# schem5.net
KiCad netlist of a schematic drawn in EAGLE
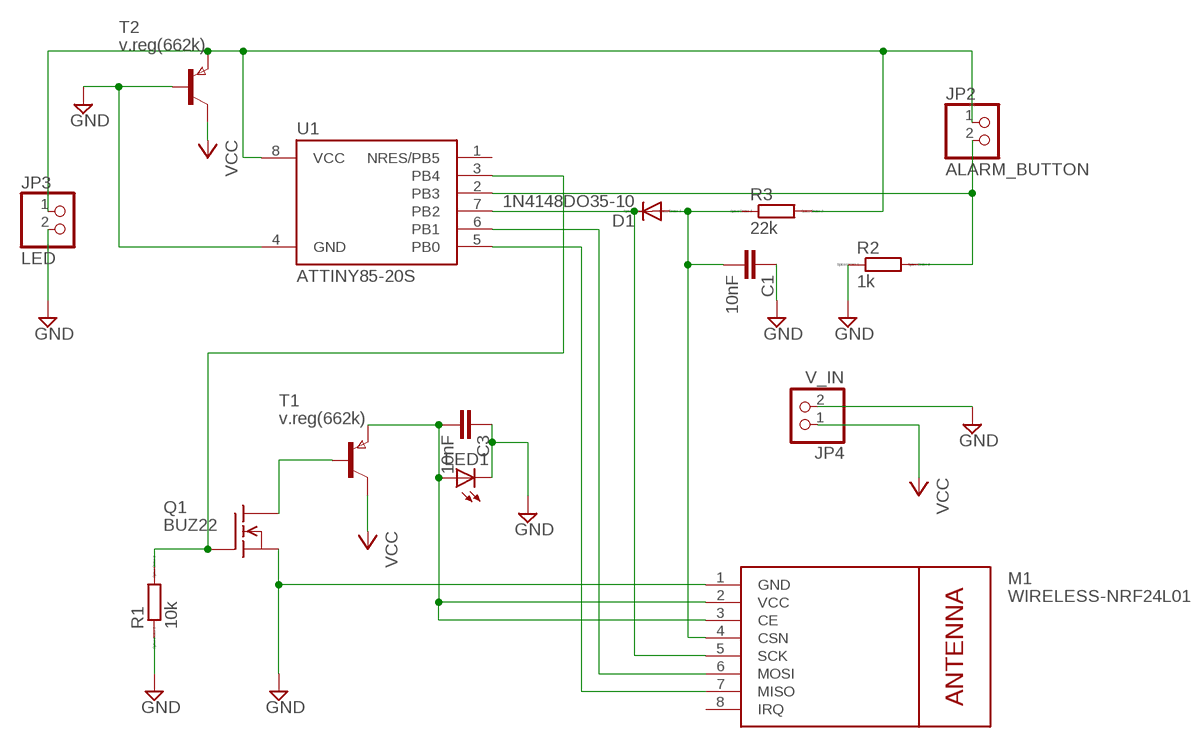
[diagram p0: schematic, sheet 1]

(export (version "E")
  (design (tool "Eeschema 10.0.6"))
  (components
    (comp (ref "C1")
      (value "10nF")
      (footprint "eagle-import:C2.5-2")
      (libsource (lib "eagle-import") (part "C2.5/2"))
    )
    (comp (ref "C3")
      (value "10nF")
      (footprint "eagle-import:C2.5-2")
      (libsource (lib "eagle-import") (part "C2.5/2"))
    )
    (comp (ref "D1")
      (value "1N4148DO35-10")
      (footprint "eagle-import:DO35-10")
      (libsource (lib "eagle-import") (part "1N4148DO35-10"))
    )
    (comp (ref "JP2")
      (value "ALARM_BUTTON")
      (footprint "eagle-import:1X02")
      (libsource (lib "eagle-import") (part "PINHD-1X2"))
    )
    (comp (ref "JP3")
      (value "LED")
      (footprint "eagle-import:1X02")
      (libsource (lib "eagle-import") (part "PINHD-1X2"))
    )
    (comp (ref "JP4")
      (value "V_IN")
      (footprint "eagle-import:1X02")
      (libsource (lib "eagle-import") (part "PINHD-1X2"))
    )
    (comp (ref "LED1")
      (value "LED5MM")
      (footprint "eagle-import:LED5MM")
      (libsource (lib "eagle-import") (part "LED5MM"))
    )
    (comp (ref "M1")
      (value "WIRELESS-NRF24L01")
      (footprint "eagle-import:WIRELESS-NRF24L01")
      (libsource (lib "eagle-import") (part "WIRELESS-NRF24L01"))
    )
    (comp (ref "Q1")
      (value "BUZ22")
      (footprint "eagle-import:TO220")
      (libsource (lib "eagle-import") (part "BUZ22"))
    )
    (comp (ref "R1")
      (value "10k")
      (footprint "eagle-import:0204_7")
      (libsource (lib "eagle-import") (part "R0204/7"))
    )
    (comp (ref "R2")
      (value "1k")
      (footprint "eagle-import:0204_7")
      (libsource (lib "eagle-import") (part "R0204/7"))
    )
    (comp (ref "R3")
      (value "22k")
      (footprint "eagle-import:0204_7")
      (libsource (lib "eagle-import") (part "R0204/7"))
    )
    (comp (ref "T1")
      (value "v.reg(662k)")
      (footprint "eagle-import:SOT323")
      (fields (field (name "MPN") "2DB1689-7"))
      (libsource (lib "eagle-import") (part "PNPSOT323"))
    )
    (comp (ref "T2")
      (value "v.reg(662k)")
      (footprint "eagle-import:SOT323")
      (fields (field (name "MPN") "2DB1689-7"))
      (libsource (lib "eagle-import") (part "PNPSOT323"))
    )
    (comp (ref "U1")
      (value "ATTINY85-20S")
      (footprint "eagle-import:SOIC8_EIAJ_208MIL")
      (libsource (lib "eagle-import") (part "ATTINY85S-20"))
    )
  )
  (nets
    (net (code "1") (name "GND") (class "Default")
      (node (ref "C1") (pin "1") (pinfunction "1_1") (pintype "passive"))
      (node (ref "C3") (pin "1") (pinfunction "1_1") (pintype "passive"))
      (node (ref "JP3") (pin "2") (pinfunction "2_2") (pintype "passive"))
      (node (ref "JP4") (pin "2") (pinfunction "2_2") (pintype "passive"))
      (node (ref "LED1") (pin "K") (pinfunction "C_K") (pintype "passive"))
      (node (ref "M1") (pin "1") (pinfunction "GND_1") (pintype "power_in"))
      (node (ref "Q1") (pin "3") (pinfunction "S_3") (pintype "passive"))
      (node (ref "R1") (pin "1") (pinfunction "1_1") (pintype "passive"))
      (node (ref "R2") (pin "1") (pinfunction "1_1") (pintype "passive"))
      (node (ref "T2") (pin "2") (pinfunction "B_2") (pintype "passive"))
      (node (ref "U1") (pin "4") (pinfunction "GND_4") (pintype "power_in"))
    )
    (net (code "2") (name "Net-(M1-CE)") (class "Default")
      (node (ref "C3") (pin "2") (pinfunction "2_2") (pintype "passive"))
      (node (ref "LED1") (pin "A") (pinfunction "A_A") (pintype "passive"))
      (node (ref "M1") (pin "2") (pinfunction "VCC_2") (pintype "power_in"))
      (node (ref "M1") (pin "3") (pinfunction "CE_3") (pintype "bidirectional"))
      (node (ref "T1") (pin "3") (pinfunction "E_3") (pintype "passive"))
    )
    (net (code "3") (name "Net-(M1-CSN)") (class "Default")
      (node (ref "C1") (pin "2") (pinfunction "2_2") (pintype "passive"))
      (node (ref "D1") (pin "A") (pinfunction "A_A") (pintype "passive"))
      (node (ref "M1") (pin "4") (pinfunction "CSN_4") (pintype "bidirectional"))
      (node (ref "R3") (pin "1") (pinfunction "1_1") (pintype "passive"))
    )
    (net (code "4") (name "Net-(M1-MISO)") (class "Default")
      (node (ref "M1") (pin "7") (pinfunction "MISO_7") (pintype "bidirectional"))
      (node (ref "U1") (pin "5") (pinfunction "PB0_5") (pintype "bidirectional"))
    )
    (net (code "5") (name "Net-(M1-MOSI)") (class "Default")
      (node (ref "M1") (pin "6") (pinfunction "MOSI_6") (pintype "bidirectional"))
      (node (ref "U1") (pin "6") (pinfunction "PB1_6") (pintype "bidirectional"))
    )
    (net (code "6") (name "Net-(M1-SCK)") (class "Default")
      (node (ref "D1") (pin "C") (pinfunction "C_C") (pintype "passive"))
      (node (ref "M1") (pin "5") (pinfunction "SCK_5") (pintype "bidirectional"))
      (node (ref "U1") (pin "7") (pinfunction "PB2_7") (pintype "bidirectional"))
    )
    (net (code "7") (name "Net-(Q1-D)") (class "Default")
      (node (ref "Q1") (pin "2") (pinfunction "D_2") (pintype "passive"))
      (node (ref "T1") (pin "2") (pinfunction "B_2") (pintype "passive"))
    )
    (net (code "8") (name "Net-(Q1-G)") (class "Default")
      (node (ref "Q1") (pin "1") (pinfunction "G_1") (pintype "passive"))
      (node (ref "R1") (pin "2") (pinfunction "2_2") (pintype "passive"))
      (node (ref "U1") (pin "3") (pinfunction "PB4_3") (pintype "bidirectional"))
    )
    (net (code "9") (name "Net-(T2-E)") (class "Default")
      (node (ref "JP2") (pin "1") (pinfunction "1_1") (pintype "passive"))
      (node (ref "JP3") (pin "1") (pinfunction "1_1") (pintype "passive"))
      (node (ref "R3") (pin "2") (pinfunction "2_2") (pintype "passive"))
      (node (ref "T2") (pin "3") (pinfunction "E_3") (pintype "passive"))
      (node (ref "U1") (pin "8") (pinfunction "VCC_8") (pintype "power_in"))
    )
    (net (code "10") (name "Net-(U1-PB3)") (class "Default")
      (node (ref "JP2") (pin "2") (pinfunction "2_2") (pintype "passive"))
      (node (ref "R2") (pin "2") (pinfunction "2_2") (pintype "passive"))
      (node (ref "U1") (pin "2") (pinfunction "PB3_2") (pintype "bidirectional"))
    )
    (net (code "11") (name "VCC") (class "Default")
      (node (ref "JP4") (pin "1") (pinfunction "1_1") (pintype "passive"))
      (node (ref "T1") (pin "1") (pinfunction "C_1") (pintype "passive"))
      (node (ref "T2") (pin "1") (pinfunction "C_1") (pintype "passive"))
    )
    (net (code "12") (name "unconnected-(M1-IRQ-Pad8)") (class "Default")
      (node (ref "M1") (pin "8") (pinfunction "IRQ_8") (pintype "bidirectional"))
    )
    (net (code "13") (name "unconnected-(U1-NRES{slash}PB5-Pad1)") (class "Default")
      (node (ref "U1") (pin "1") (pinfunction "NRES/PB5_1") (pintype "bidirectional"))
    )
  )
)
